# MSP_part_PCB_new.net
KiCad netlist of a schematic drawn in EAGLE
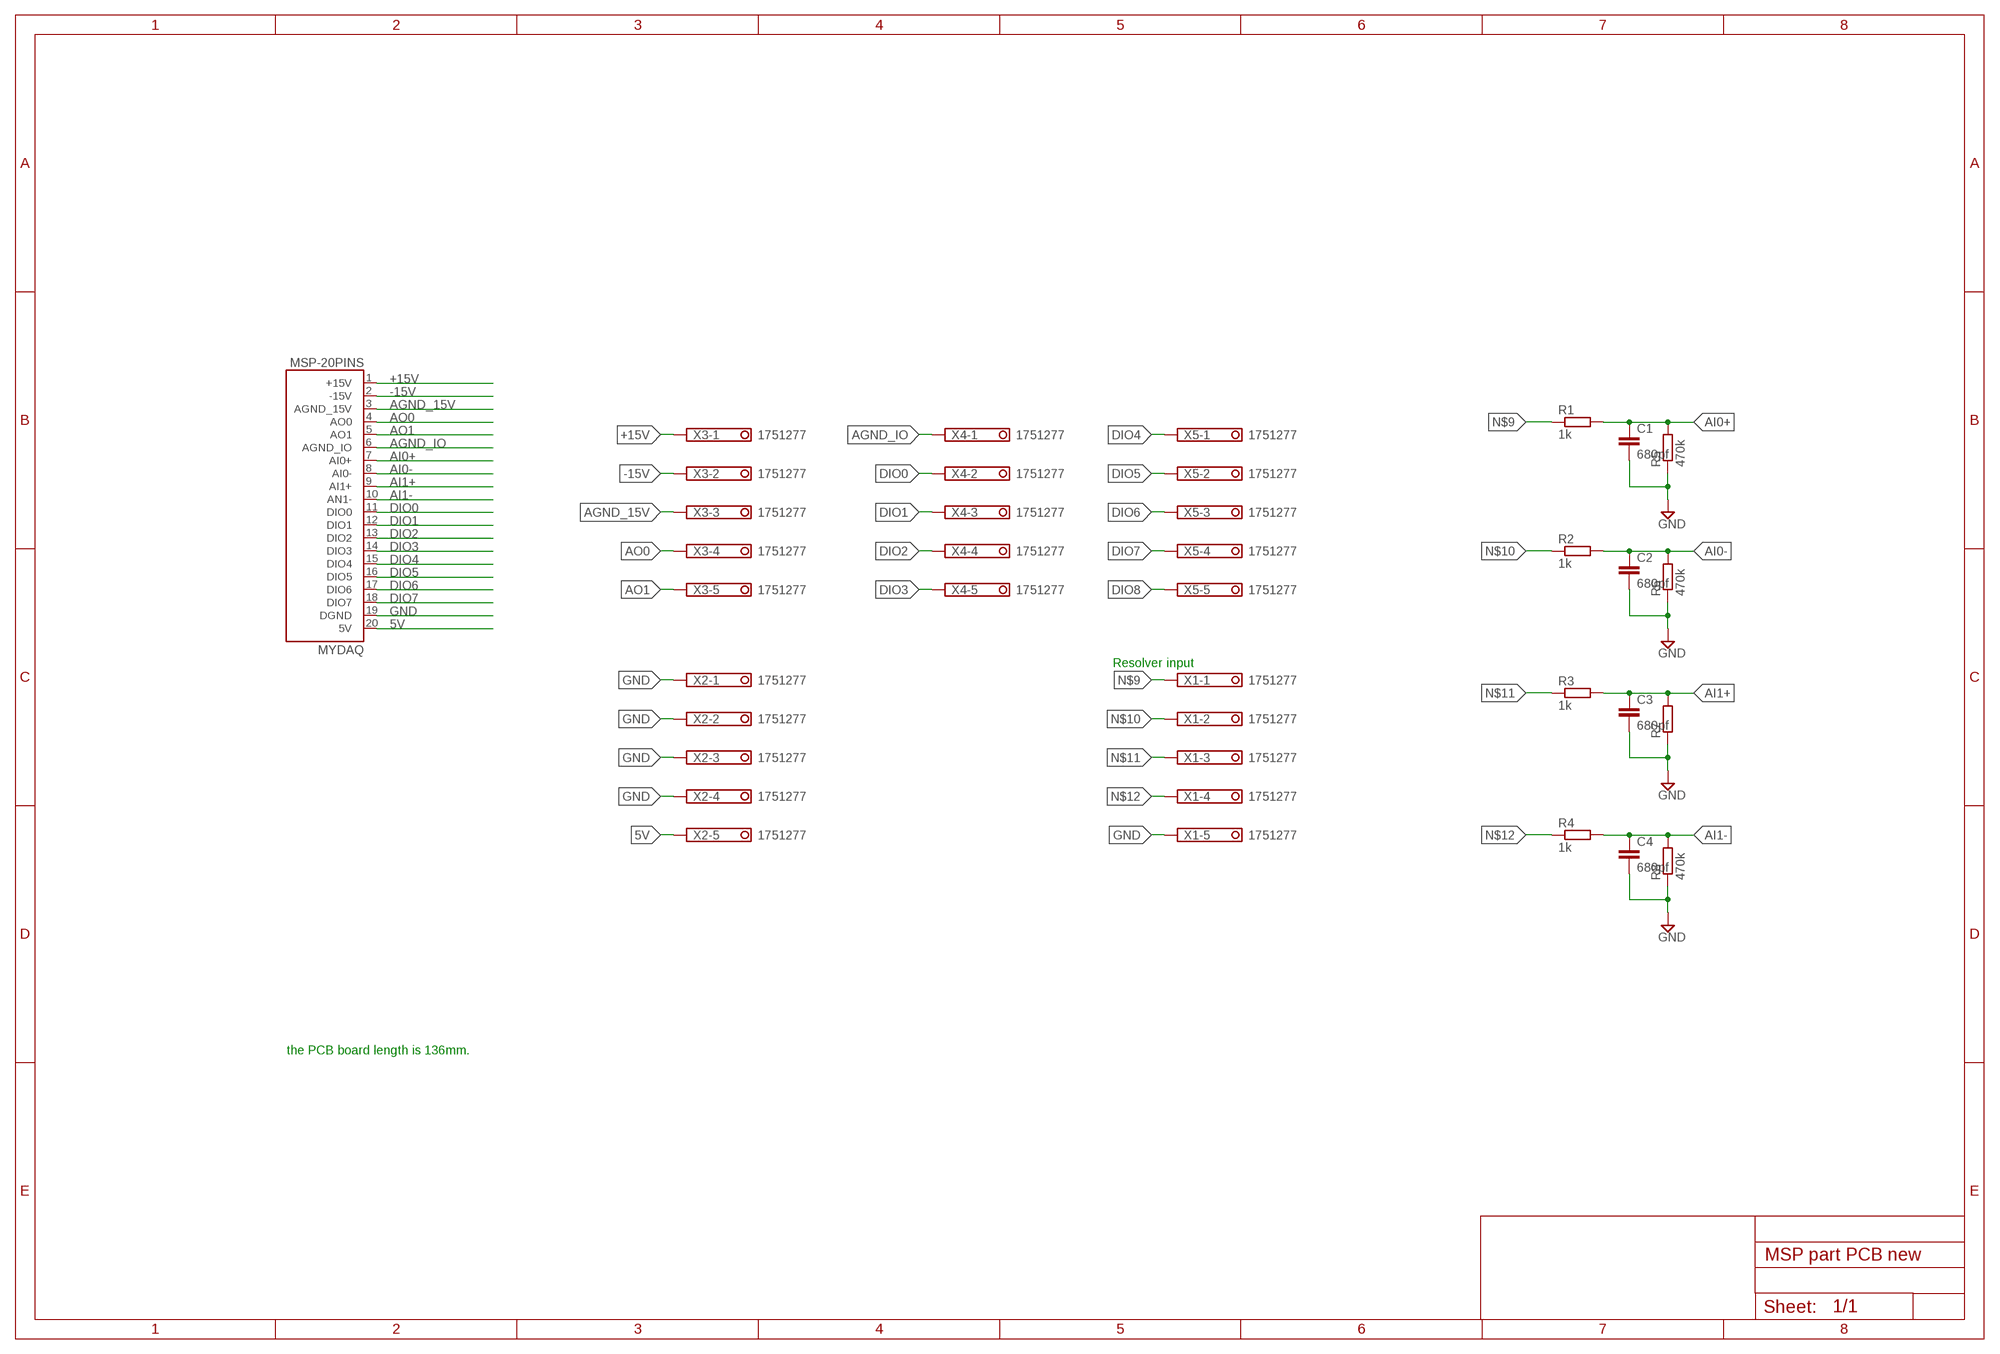
[diagram p0: schematic, sheet 1]

(export (version "E")
  (design (tool "Eeschema 10.0.6"))
  (components
    (comp (ref "C1")
      (value "680pf")
      (footprint "eagle-import:C050-024X044")
      (libsource (lib "eagle-import") (part "C-EU050-024X044"))
    )
    (comp (ref "C2")
      (value "680pf")
      (footprint "eagle-import:C050-024X044")
      (libsource (lib "eagle-import") (part "C-EU050-024X044"))
    )
    (comp (ref "C3")
      (value "680pf")
      (footprint "eagle-import:C050-024X044")
      (libsource (lib "eagle-import") (part "C-EU050-024X044"))
    )
    (comp (ref "C4")
      (value "680pf")
      (footprint "eagle-import:C050-024X044")
      (libsource (lib "eagle-import") (part "C-EU050-024X044"))
    )
    (comp (ref "MSP-20PINS")
      (value "MYDAQ")
      (footprint "eagle-import:3.81MM_TERMINAL_BLOCK_FEMALE_LOCKING")
      (libsource (lib "eagle-import") (part "MYDAQ"))
    )
    (comp (ref "R1")
      (value "1k")
      (footprint "eagle-import:0204_7")
      (libsource (lib "eagle-import") (part "R-EU_0204/7"))
    )
    (comp (ref "R2")
      (value "1k")
      (footprint "eagle-import:0204_7")
      (libsource (lib "eagle-import") (part "R-EU_0204/7"))
    )
    (comp (ref "R3")
      (value "1k")
      (footprint "eagle-import:0204_7")
      (libsource (lib "eagle-import") (part "R-EU_0204/7"))
    )
    (comp (ref "R4")
      (value "1k")
      (footprint "eagle-import:0204_7")
      (libsource (lib "eagle-import") (part "R-EU_0204/7"))
    )
    (comp (ref "R5")
      (value "470k")
      (footprint "eagle-import:0204_7")
      (libsource (lib "eagle-import") (part "R-EU_0204/7"))
    )
    (comp (ref "R6")
      (value "470k")
      (footprint "eagle-import:0204_7")
      (libsource (lib "eagle-import") (part "R-EU_0204/7"))
    )
    (comp (ref "R7")
      (value "R-EU_0204/7")
      (footprint "eagle-import:0204_7")
      (libsource (lib "eagle-import") (part "R-EU_0204/7"))
    )
    (comp (ref "R8")
      (value "470k")
      (footprint "eagle-import:0204_7")
      (libsource (lib "eagle-import") (part "R-EU_0204/7"))
    )
    (comp (ref "X1")
      (value "1751277")
      (footprint "eagle-import:1751277")
      (libsource (lib "eagle-import") (part "1751277"))
    )
    (comp (ref "X2")
      (value "1751277")
      (footprint "eagle-import:1751277")
      (libsource (lib "eagle-import") (part "1751277"))
    )
    (comp (ref "X3")
      (value "1751277")
      (footprint "eagle-import:1751277")
      (libsource (lib "eagle-import") (part "1751277"))
    )
    (comp (ref "X4")
      (value "1751277")
      (footprint "eagle-import:1751277")
      (libsource (lib "eagle-import") (part "1751277"))
    )
    (comp (ref "X5")
      (value "1751277")
      (footprint "eagle-import:1751277")
      (libsource (lib "eagle-import") (part "1751277"))
    )
  )
  (nets
    (net (code "1") (name "+15V") (class "Default")
      (node (ref "MSP-20PINS") (pin "1") (pinfunction "+15V_1") (pintype "power_in"))
      (node (ref "X3") (pin "1") (pinfunction "K_1") (pintype "passive"))
    )
    (net (code "2") (name "-15V") (class "Default")
      (node (ref "MSP-20PINS") (pin "2") (pinfunction "-15V_2") (pintype "power_in"))
      (node (ref "X3") (pin "2") (pinfunction "K_2") (pintype "passive"))
    )
    (net (code "3") (name "5V") (class "Default")
      (node (ref "MSP-20PINS") (pin "20") (pinfunction "5V_20") (pintype "power_in"))
      (node (ref "X2") (pin "5") (pinfunction "K_5") (pintype "passive"))
    )
    (net (code "4") (name "AGND_15V") (class "Default")
      (node (ref "MSP-20PINS") (pin "3") (pinfunction "AGND_15V_3") (pintype "power_in"))
      (node (ref "X3") (pin "3") (pinfunction "K_3") (pintype "passive"))
    )
    (net (code "5") (name "AGND_IO") (class "Default")
      (node (ref "MSP-20PINS") (pin "6") (pinfunction "AGND_IO_6") (pintype "power_in"))
      (node (ref "X4") (pin "1") (pinfunction "K_1") (pintype "passive"))
    )
    (net (code "6") (name "AI0+") (class "Default")
      (node (ref "C1") (pin "1") (pinfunction "1_1") (pintype "passive"))
      (node (ref "MSP-20PINS") (pin "7") (pinfunction "AI0+_7") (pintype "input"))
      (node (ref "R1") (pin "2") (pinfunction "2_2") (pintype "passive"))
      (node (ref "R5") (pin "2") (pinfunction "2_2") (pintype "passive"))
    )
    (net (code "7") (name "AI0-") (class "Default")
      (node (ref "C2") (pin "1") (pinfunction "1_1") (pintype "passive"))
      (node (ref "MSP-20PINS") (pin "8") (pinfunction "AI0-_8") (pintype "input"))
      (node (ref "R2") (pin "2") (pinfunction "2_2") (pintype "passive"))
      (node (ref "R6") (pin "2") (pinfunction "2_2") (pintype "passive"))
    )
    (net (code "8") (name "AI1+") (class "Default")
      (node (ref "C3") (pin "1") (pinfunction "1_1") (pintype "passive"))
      (node (ref "MSP-20PINS") (pin "9") (pinfunction "AI1+_9") (pintype "input"))
      (node (ref "R3") (pin "2") (pinfunction "2_2") (pintype "passive"))
      (node (ref "R7") (pin "2") (pinfunction "2_2") (pintype "passive"))
    )
    (net (code "9") (name "AI1-") (class "Default")
      (node (ref "C4") (pin "1") (pinfunction "1_1") (pintype "passive"))
      (node (ref "MSP-20PINS") (pin "10") (pinfunction "AN1-_10") (pintype "input"))
      (node (ref "R4") (pin "2") (pinfunction "2_2") (pintype "passive"))
      (node (ref "R8") (pin "2") (pinfunction "2_2") (pintype "passive"))
    )
    (net (code "10") (name "AO0") (class "Default")
      (node (ref "MSP-20PINS") (pin "4") (pinfunction "AO0_4") (pintype "output"))
      (node (ref "X3") (pin "4") (pinfunction "K_4") (pintype "passive"))
    )
    (net (code "11") (name "AO1") (class "Default")
      (node (ref "MSP-20PINS") (pin "5") (pinfunction "AO1_5") (pintype "output"))
      (node (ref "X3") (pin "5") (pinfunction "K_5") (pintype "passive"))
    )
    (net (code "12") (name "DIO0") (class "Default")
      (node (ref "MSP-20PINS") (pin "11") (pinfunction "DIO0_11") (pintype "bidirectional"))
      (node (ref "X4") (pin "2") (pinfunction "K_2") (pintype "passive"))
    )
    (net (code "13") (name "DIO1") (class "Default")
      (node (ref "MSP-20PINS") (pin "12") (pinfunction "DIO1_12") (pintype "bidirectional"))
      (node (ref "X4") (pin "3") (pinfunction "K_3") (pintype "passive"))
    )
    (net (code "14") (name "DIO2") (class "Default")
      (node (ref "MSP-20PINS") (pin "13") (pinfunction "DIO2_13") (pintype "bidirectional"))
      (node (ref "X4") (pin "4") (pinfunction "K_4") (pintype "passive"))
    )
    (net (code "15") (name "DIO3") (class "Default")
      (node (ref "MSP-20PINS") (pin "14") (pinfunction "DIO3_14") (pintype "bidirectional"))
      (node (ref "X4") (pin "5") (pinfunction "K_5") (pintype "passive"))
    )
    (net (code "16") (name "DIO4") (class "Default")
      (node (ref "MSP-20PINS") (pin "15") (pinfunction "DIO4_15") (pintype "bidirectional"))
      (node (ref "X5") (pin "1") (pinfunction "K_1") (pintype "passive"))
    )
    (net (code "17") (name "DIO5") (class "Default")
      (node (ref "MSP-20PINS") (pin "16") (pinfunction "DIO5_16") (pintype "bidirectional"))
      (node (ref "X5") (pin "2") (pinfunction "K_2") (pintype "passive"))
    )
    (net (code "18") (name "DIO6") (class "Default")
      (node (ref "MSP-20PINS") (pin "17") (pinfunction "DIO6_17") (pintype "bidirectional"))
      (node (ref "X5") (pin "3") (pinfunction "K_3") (pintype "passive"))
    )
    (net (code "19") (name "DIO7") (class "Default")
      (node (ref "MSP-20PINS") (pin "18") (pinfunction "DIO7_18") (pintype "bidirectional"))
      (node (ref "X5") (pin "4") (pinfunction "K_4") (pintype "passive"))
    )
    (net (code "20") (name "DIO8") (class "Default")
      (node (ref "X5") (pin "5") (pinfunction "K_5") (pintype "passive"))
    )
    (net (code "21") (name "GND") (class "Default")
      (node (ref "C1") (pin "2") (pinfunction "2_2") (pintype "passive"))
      (node (ref "C2") (pin "2") (pinfunction "2_2") (pintype "passive"))
      (node (ref "C3") (pin "2") (pinfunction "2_2") (pintype "passive"))
      (node (ref "C4") (pin "2") (pinfunction "2_2") (pintype "passive"))
      (node (ref "MSP-20PINS") (pin "19") (pinfunction "DGND_19") (pintype "power_in"))
      (node (ref "R5") (pin "1") (pinfunction "1_1") (pintype "passive"))
      (node (ref "R6") (pin "1") (pinfunction "1_1") (pintype "passive"))
      (node (ref "R7") (pin "1") (pinfunction "1_1") (pintype "passive"))
      (node (ref "R8") (pin "1") (pinfunction "1_1") (pintype "passive"))
      (node (ref "X1") (pin "5") (pinfunction "K_5") (pintype "passive"))
      (node (ref "X2") (pin "1") (pinfunction "K_1") (pintype "passive"))
      (node (ref "X2") (pin "2") (pinfunction "K_2") (pintype "passive"))
      (node (ref "X2") (pin "3") (pinfunction "K_3") (pintype "passive"))
      (node (ref "X2") (pin "4") (pinfunction "K_4") (pintype "passive"))
    )
    (net (code "22") (name "N$9") (class "Default")
      (node (ref "R1") (pin "1") (pinfunction "1_1") (pintype "passive"))
      (node (ref "X1") (pin "1") (pinfunction "K_1") (pintype "passive"))
    )
    (net (code "23") (name "N$10") (class "Default")
      (node (ref "R2") (pin "1") (pinfunction "1_1") (pintype "passive"))
      (node (ref "X1") (pin "2") (pinfunction "K_2") (pintype "passive"))
    )
    (net (code "24") (name "N$11") (class "Default")
      (node (ref "R3") (pin "1") (pinfunction "1_1") (pintype "passive"))
      (node (ref "X1") (pin "3") (pinfunction "K_3") (pintype "passive"))
    )
    (net (code "25") (name "N$12") (class "Default")
      (node (ref "R4") (pin "1") (pinfunction "1_1") (pintype "passive"))
      (node (ref "X1") (pin "4") (pinfunction "K_4") (pintype "passive"))
    )
  )
)
